# TMP006.net
KiCad netlist of a schematic drawn in EAGLE
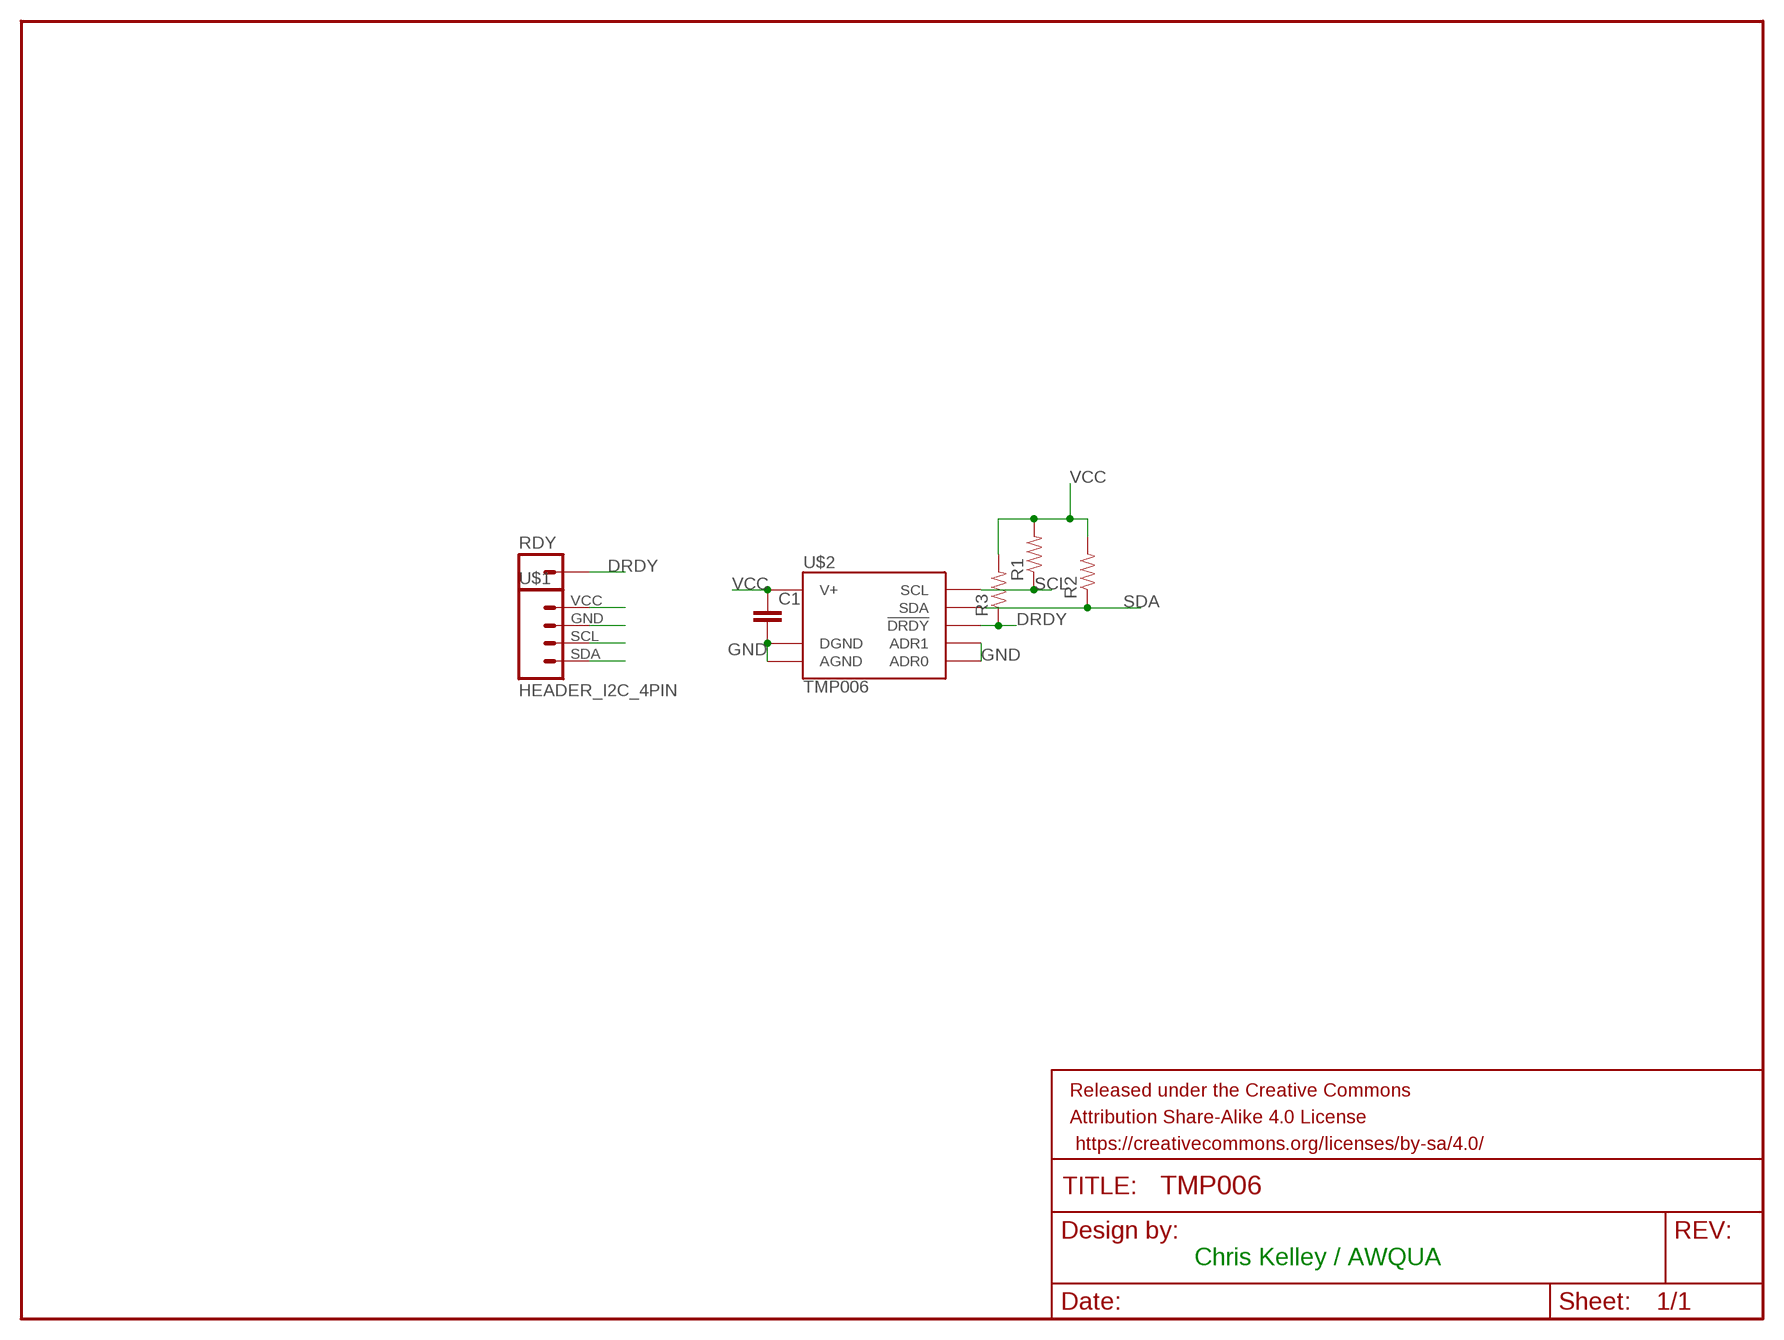
[diagram p0: schematic, sheet 1]

(export (version "E")
  (design (tool "Eeschema 10.0.6"))
  (components
    (comp (ref "C1")
      (value "CAP0603-CAP")
      (footprint "eagle-import:0603-CAP")
      (libsource (lib "eagle-import") (part "CAP0603-CAP"))
    )
    (comp (ref "FRAME1")
      (value "FRAME-LETTER")
      (footprint "eagle-import:CREATIVE_COMMONS")
      (libsource (lib "eagle-import") (part "FRAME-LETTER"))
    )
    (comp (ref "R1")
      (value "RESISTOR0603-RES")
      (footprint "eagle-import:0603-RES")
      (libsource (lib "eagle-import") (part "RESISTOR0603-RES"))
    )
    (comp (ref "R2")
      (value "RESISTOR0603-RES")
      (footprint "eagle-import:0603-RES")
      (libsource (lib "eagle-import") (part "RESISTOR0603-RES"))
    )
    (comp (ref "R3")
      (value "RESISTOR0603-RES")
      (footprint "eagle-import:0603-RES")
      (libsource (lib "eagle-import") (part "RESISTOR0603-RES"))
    )
    (comp (ref "RDY")
      (value "M01PTH")
      (footprint "eagle-import:1X01")
      (libsource (lib "eagle-import") (part "M01PTH"))
    )
    (comp (ref "U$1")
      (value "HEADER_I2C_4PIN")
      (footprint "eagle-import:HEADER_I2C_4PIN")
      (libsource (lib "eagle-import") (part "HEADER_I2C_4PIN"))
    )
    (comp (ref "U$2")
      (value "TMP006")
      (footprint "eagle-import:TMP006")
      (libsource (lib "eagle-import") (part "TMP006"))
    )
  )
  (nets
    (net (code "1") (name "/DRDY") (class "Default")
      (node (ref "R3") (pin "1") (pinfunction "1_1") (pintype "passive"))
      (node (ref "RDY") (pin "1") (pinfunction "1_1") (pintype "passive"))
      (node (ref "U$2") (pin "DRDY") (pinfunction "~{DRDY}_DRDY") (pintype "bidirectional"))
    )
    (net (code "2") (name "/GND") (class "Default")
      (node (ref "C1") (pin "2") (pinfunction "2_2") (pintype "passive"))
      (node (ref "U$1") (pin "GND") (pinfunction "GND_GND") (pintype "passive"))
      (node (ref "U$2") (pin "ADR0") (pinfunction "ADR0_ADR0") (pintype "bidirectional"))
      (node (ref "U$2") (pin "ADR1") (pinfunction "ADR1_ADR1") (pintype "bidirectional"))
      (node (ref "U$2") (pin "AGND") (pinfunction "AGND_AGND") (pintype "bidirectional"))
      (node (ref "U$2") (pin "DGND") (pinfunction "DGND_DGND") (pintype "bidirectional"))
    )
    (net (code "3") (name "/SCL") (class "Default")
      (node (ref "R1") (pin "1") (pinfunction "1_1") (pintype "passive"))
      (node (ref "U$1") (pin "SCL") (pinfunction "SCL_SCL") (pintype "passive"))
      (node (ref "U$2") (pin "SCL") (pinfunction "SCL_SCL") (pintype "bidirectional"))
    )
    (net (code "4") (name "/SDA") (class "Default")
      (node (ref "R2") (pin "1") (pinfunction "1_1") (pintype "passive"))
      (node (ref "U$1") (pin "SDA") (pinfunction "SDA_SDA") (pintype "passive"))
      (node (ref "U$2") (pin "SDA") (pinfunction "SDA_SDA") (pintype "bidirectional"))
    )
    (net (code "5") (name "/VCC") (class "Default")
      (node (ref "C1") (pin "1") (pinfunction "1_1") (pintype "passive"))
      (node (ref "R1") (pin "2") (pinfunction "2_2") (pintype "passive"))
      (node (ref "R2") (pin "2") (pinfunction "2_2") (pintype "passive"))
      (node (ref "R3") (pin "2") (pinfunction "2_2") (pintype "passive"))
      (node (ref "U$1") (pin "VCC") (pinfunction "VCC_VCC") (pintype "passive"))
      (node (ref "U$2") (pin "VCC") (pinfunction "V+_VCC") (pintype "bidirectional"))
    )
  )
)
